# ADC_RESET.net
KiCad netlist of a schematic drawn in Altium Designer
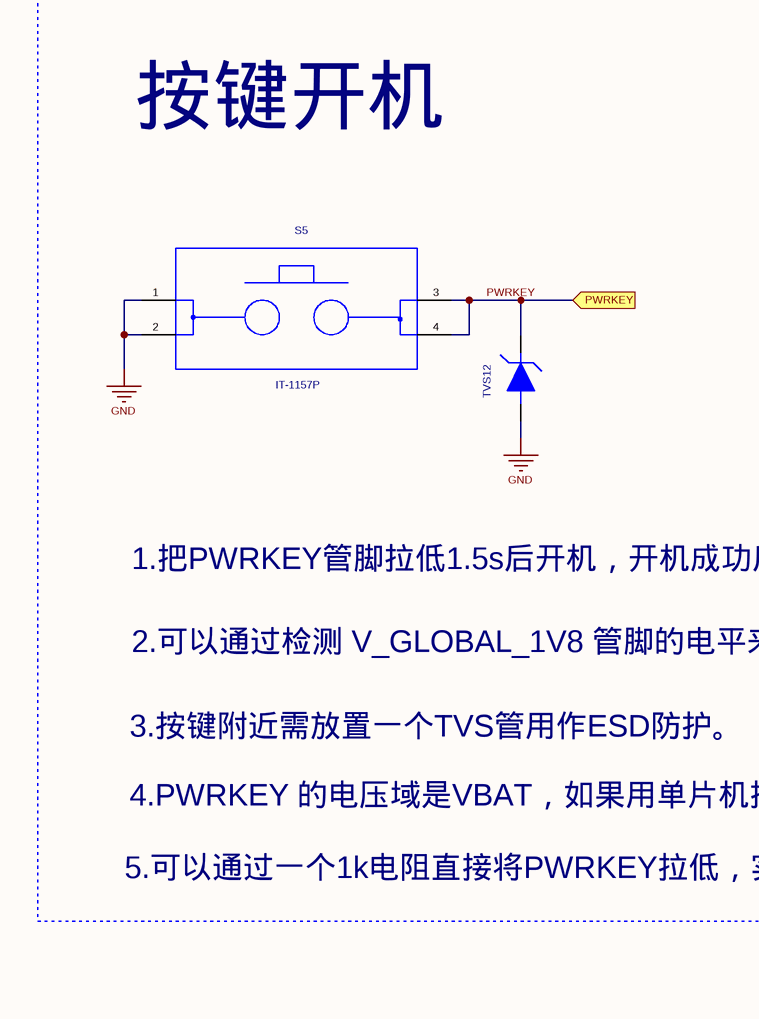
[diagram p0: ADC_RESET.SchDoc, top left]
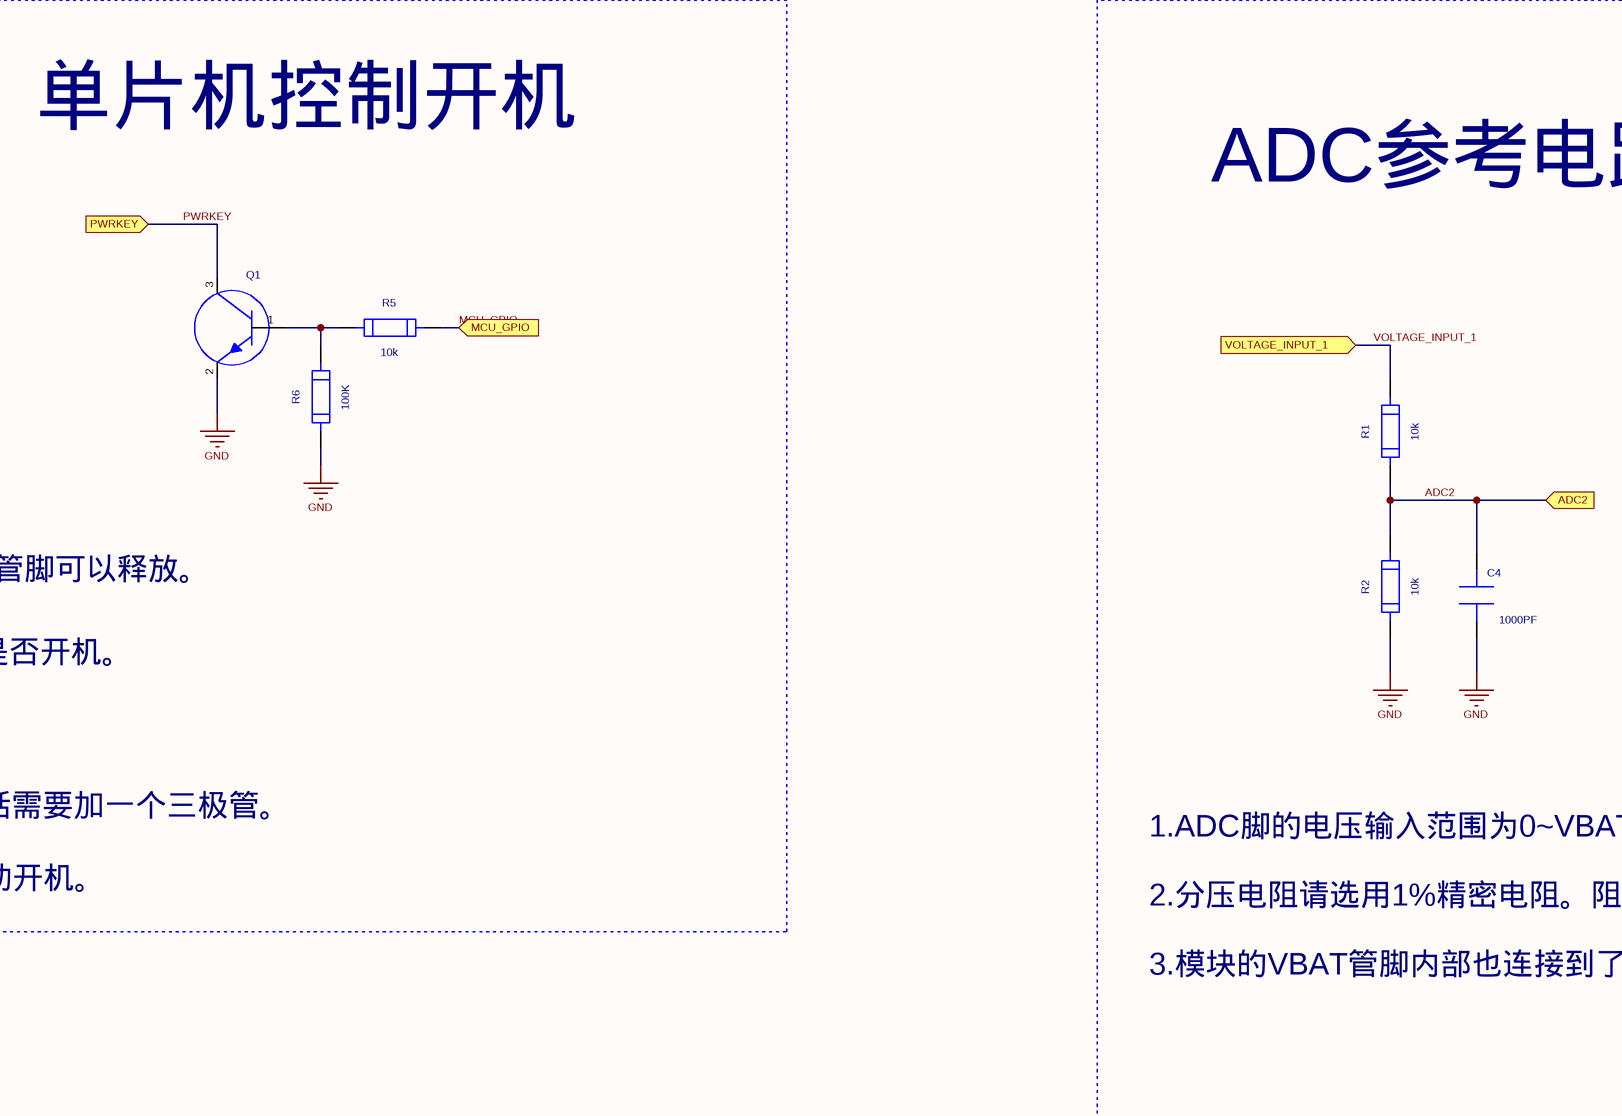
[diagram p1: ADC_RESET.SchDoc, top middle]
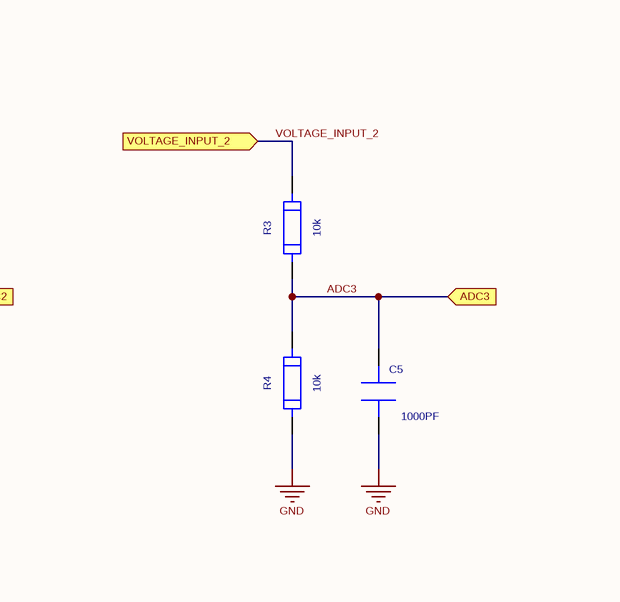
[diagram p2: ADC_RESET.SchDoc, top right]
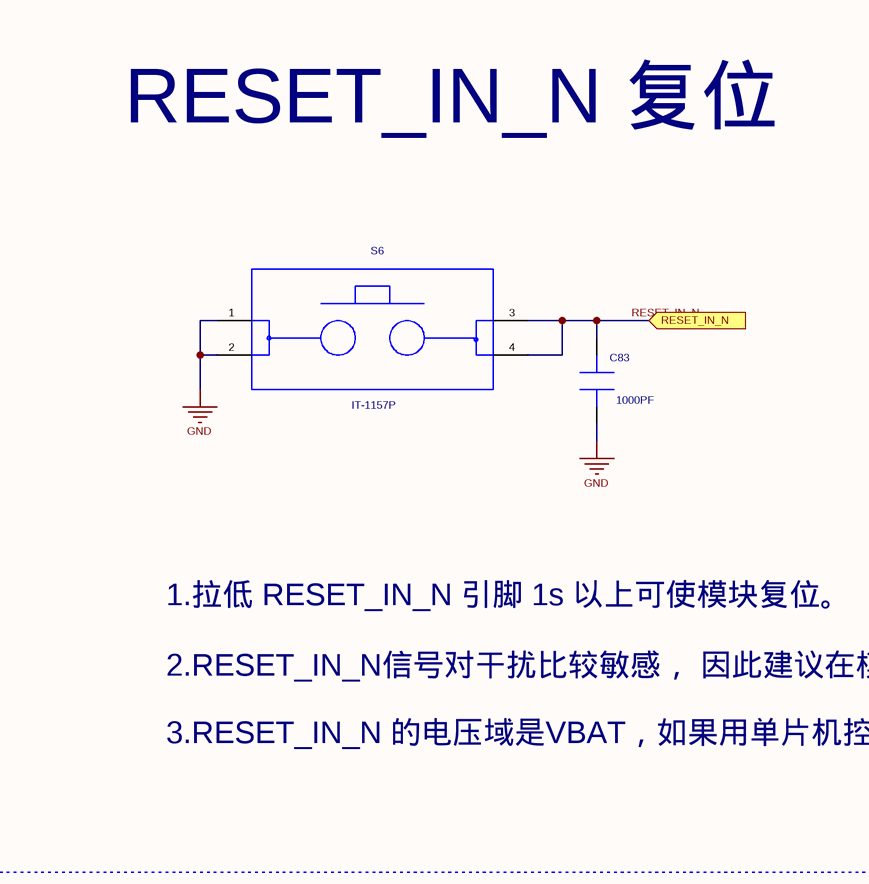
[diagram p3: ADC_RESET.SchDoc, bottom left]
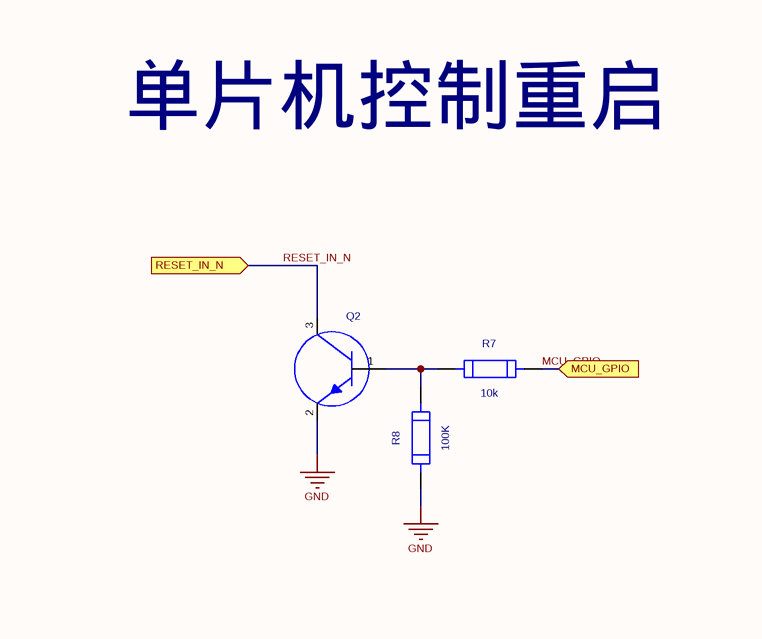
[diagram p4: ADC_RESET.SchDoc, bottom middle]
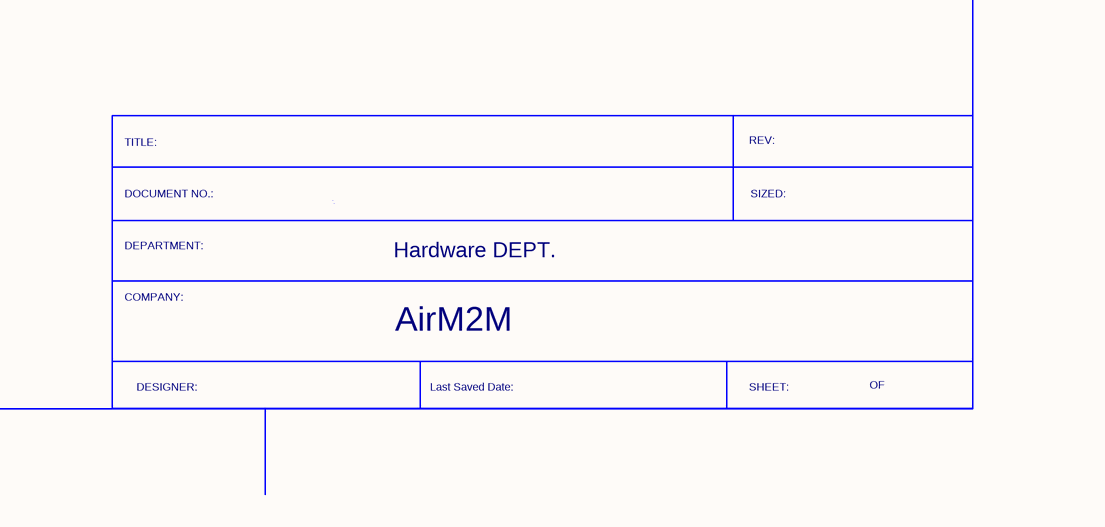
[diagram p5: ADC_RESET.SchDoc, bottom right]

(export (version "E")
  (design (tool "Eeschema 10.0.6"))
  (components
    (comp (ref "C4")
      (value "1000PF")
      (footprint "SC0402")
      (description "CAP CER X7R;1000PF;+/-10%;50V;0402;0.5mm;ROHS")
      (fields (field (name "TOLERANCE") "+/-10%") (field (name "Comment") "CAP-1000PF-0402-X7R"))
      (libsource (lib "*") (part "CAP-1000PF-0402-X7R"))
    )
    (comp (ref "C5")
      (value "1000PF")
      (footprint "SC0402")
      (description "CAP CER X7R;1000PF;+/-10%;50V;0402;0.5mm;ROHS")
      (fields (field (name "TOLERANCE") "+/-10%") (field (name "Comment") "CAP-1000PF-0402-X7R"))
      (libsource (lib "*") (part "CAP-1000PF-0402-X7R"))
    )
    (comp (ref "C83")
      (value "1000PF")
      (footprint "SC0402")
      (description "CAP CER X7R;1000PF;+/-10%;50V;0402;0.5mm;ROHS")
      (fields (field (name "TOLERANCE") "+/-10%") (field (name "Comment") "CAP-1000PF-0402-X7R"))
      (libsource (lib "*") (part "CAP-1000PF-0402-X7R"))
    )
    (comp (ref "Q1")
      (value "TRIODE-NPN-MMBT3904")
      (footprint "SOT-23(MMBT3904)")
      (description "Transistor;NPN;40V;200mA;SOT23;1.1mm;ROHS")
      (libsource (lib "*") (part "TRIODE-NPN-MMBT3904"))
    )
    (comp (ref "Q2")
      (value "TRIODE-NPN-MMBT3904")
      (footprint "SOT-23(MMBT3904)")
      (description "Transistor;NPN;40V;200mA;SOT23;1.1mm;ROHS")
      (libsource (lib "*") (part "TRIODE-NPN-MMBT3904"))
    )
    (comp (ref "R1")
      (value "10k")
      (footprint "SR0402")
      (description "RES FILM;10K;+/-5%;1/16W;0402;0.4mm;ROHS")
      (fields (field (name "TOLERANCE") "+/-5%") (field (name "Comment") "RES-10K-0402"))
      (libsource (lib "*") (part "RES-10K-0402"))
    )
    (comp (ref "R2")
      (value "10k")
      (footprint "SR0402")
      (description "RES FILM;10K;+/-5%;1/16W;0402;0.4mm;ROHS")
      (fields (field (name "TOLERANCE") "+/-5%") (field (name "Comment") "RES-10K-0402"))
      (libsource (lib "*") (part "RES-10K-0402"))
    )
    (comp (ref "R3")
      (value "10k")
      (footprint "SR0402")
      (description "RES FILM;10K;+/-5%;1/16W;0402;0.4mm;ROHS")
      (fields (field (name "TOLERANCE") "+/-5%") (field (name "Comment") "RES-10K-0402"))
      (libsource (lib "*") (part "RES-10K-0402"))
    )
    (comp (ref "R4")
      (value "10k")
      (footprint "SR0402")
      (description "RES FILM;10K;+/-5%;1/16W;0402;0.4mm;ROHS")
      (fields (field (name "TOLERANCE") "+/-5%") (field (name "Comment") "RES-10K-0402"))
      (libsource (lib "*") (part "RES-10K-0402"))
    )
    (comp (ref "R5")
      (value "10k")
      (footprint "SR0402")
      (description "RES FILM;10K;+/-5%;1/16W;0402;0.4mm;ROHS")
      (fields (field (name "TOLERANCE") "+/-5%") (field (name "Comment") "RES-10K-0402"))
      (libsource (lib "*") (part "RES-10K-0402"))
    )
    (comp (ref "R6")
      (value "100K")
      (footprint "SR0402")
      (description "RES FILM;100K;+/-5%;1/16W;0402;0.4mm;ROHS")
      (fields (field (name "TOLERANCE") "+/-5%") (field (name "Comment") "RES-100K-0402"))
      (libsource (lib "*") (part "RES-100K-0402"))
    )
    (comp (ref "R7")
      (value "10k")
      (footprint "SR0402")
      (description "RES FILM;10K;+/-5%;1/16W;0402;0.4mm;ROHS")
      (fields (field (name "TOLERANCE") "+/-5%") (field (name "Comment") "RES-10K-0402"))
      (libsource (lib "*") (part "RES-10K-0402"))
    )
    (comp (ref "R8")
      (value "100K")
      (footprint "SR0402")
      (description "RES FILM;100K;+/-5%;1/16W;0402;0.4mm;ROHS")
      (fields (field (name "TOLERANCE") "+/-5%") (field (name "Comment") "RES-100K-0402"))
      (libsource (lib "*") (part "RES-100K-0402"))
    )
    (comp (ref "S5") (value "IT-1157P") (footprint "IT-1157P") (libsource (lib "*") (part "IT-1157P")))
    (comp (ref "S6") (value "IT-1157P") (footprint "IT-1157P") (libsource (lib "*") (part "IT-1157P")))
    (comp (ref "TVS12")
      (value "ESD-TVS-PESDU4581P1H")
      (footprint "DFN1006")
      (description "TVS；4.5V；双向；400W；DFN1006-2;1*0.6*0.5mm;ROHS")
      (libsource (lib "*") (part "ESD-TVS-PESDU4581P1H"))
    )
  )
  (nets
    (net (code "1") (name "/ADC2") (class "Default")
      (node (ref "C4") (pin "2") (pinfunction "2_2") (pintype "passive"))
      (node (ref "R1") (pin "1") (pinfunction "1_1") (pintype "passive"))
      (node (ref "R2") (pin "2") (pinfunction "2_2") (pintype "passive"))
    )
    (net (code "2") (name "/ADC3") (class "Default")
      (node (ref "C5") (pin "2") (pinfunction "2_2") (pintype "passive"))
      (node (ref "R3") (pin "1") (pinfunction "1_1") (pintype "passive"))
      (node (ref "R4") (pin "2") (pinfunction "2_2") (pintype "passive"))
    )
    (net (code "3") (name "/MCU_GPIO") (class "Default")
      (node (ref "R5") (pin "2") (pinfunction "2_2") (pintype "passive"))
      (node (ref "R7") (pin "2") (pinfunction "2_2") (pintype "passive"))
    )
    (net (code "4") (name "/PWRKEY") (class "Default")
      (node (ref "Q1") (pin "3") (pinfunction "3_3") (pintype "passive"))
      (node (ref "S5") (pin "3") (pinfunction "3_3") (pintype "passive"))
      (node (ref "S5") (pin "4") (pinfunction "4_4") (pintype "passive"))
      (node (ref "TVS12") (pin "1") (pinfunction "1_1") (pintype "passive"))
    )
    (net (code "5") (name "/RESET_IN_N") (class "Default")
      (node (ref "C83") (pin "1") (pinfunction "1_1") (pintype "passive"))
      (node (ref "Q2") (pin "3") (pinfunction "3_3") (pintype "passive"))
      (node (ref "S6") (pin "3") (pinfunction "3_3") (pintype "passive"))
      (node (ref "S6") (pin "4") (pinfunction "4_4") (pintype "passive"))
    )
    (net (code "6") (name "/VOLTAGE_INPUT_1") (class "Default")
      (node (ref "R1") (pin "2") (pinfunction "2_2") (pintype "passive"))
    )
    (net (code "7") (name "/VOLTAGE_INPUT_2") (class "Default")
      (node (ref "R3") (pin "2") (pinfunction "2_2") (pintype "passive"))
    )
    (net (code "8") (name "GND") (class "Default")
      (node (ref "C4") (pin "1") (pinfunction "1_1") (pintype "passive"))
      (node (ref "C5") (pin "1") (pinfunction "1_1") (pintype "passive"))
      (node (ref "C83") (pin "2") (pinfunction "2_2") (pintype "passive"))
      (node (ref "Q1") (pin "2") (pinfunction "2_2") (pintype "passive"))
      (node (ref "Q2") (pin "2") (pinfunction "2_2") (pintype "passive"))
      (node (ref "R2") (pin "1") (pinfunction "1_1") (pintype "passive"))
      (node (ref "R4") (pin "1") (pinfunction "1_1") (pintype "passive"))
      (node (ref "R6") (pin "1") (pinfunction "1_1") (pintype "passive"))
      (node (ref "R8") (pin "1") (pinfunction "1_1") (pintype "passive"))
      (node (ref "S5") (pin "1") (pinfunction "1_1") (pintype "passive"))
      (node (ref "S5") (pin "2") (pinfunction "2_2") (pintype "passive"))
      (node (ref "S5") (pin "5") (pinfunction "GND_5") (pintype "power_in"))
      (node (ref "S6") (pin "1") (pinfunction "1_1") (pintype "passive"))
      (node (ref "S6") (pin "2") (pinfunction "2_2") (pintype "passive"))
      (node (ref "S6") (pin "5") (pinfunction "GND_5") (pintype "power_in"))
      (node (ref "TVS12") (pin "2") (pinfunction "2_2") (pintype "passive"))
    )
    (net (code "9") (name "Net-(Q1-Pad1)") (class "Default")
      (node (ref "Q1") (pin "1") (pinfunction "1_1") (pintype "passive"))
      (node (ref "R5") (pin "1") (pinfunction "1_1") (pintype "passive"))
      (node (ref "R6") (pin "2") (pinfunction "2_2") (pintype "passive"))
    )
    (net (code "10") (name "Net-(Q2-Pad1)") (class "Default")
      (node (ref "Q2") (pin "1") (pinfunction "1_1") (pintype "passive"))
      (node (ref "R7") (pin "1") (pinfunction "1_1") (pintype "passive"))
      (node (ref "R8") (pin "2") (pinfunction "2_2") (pintype "passive"))
    )
  )
)
